# waltron.net
KiCad netlist of a schematic drawn in EAGLE
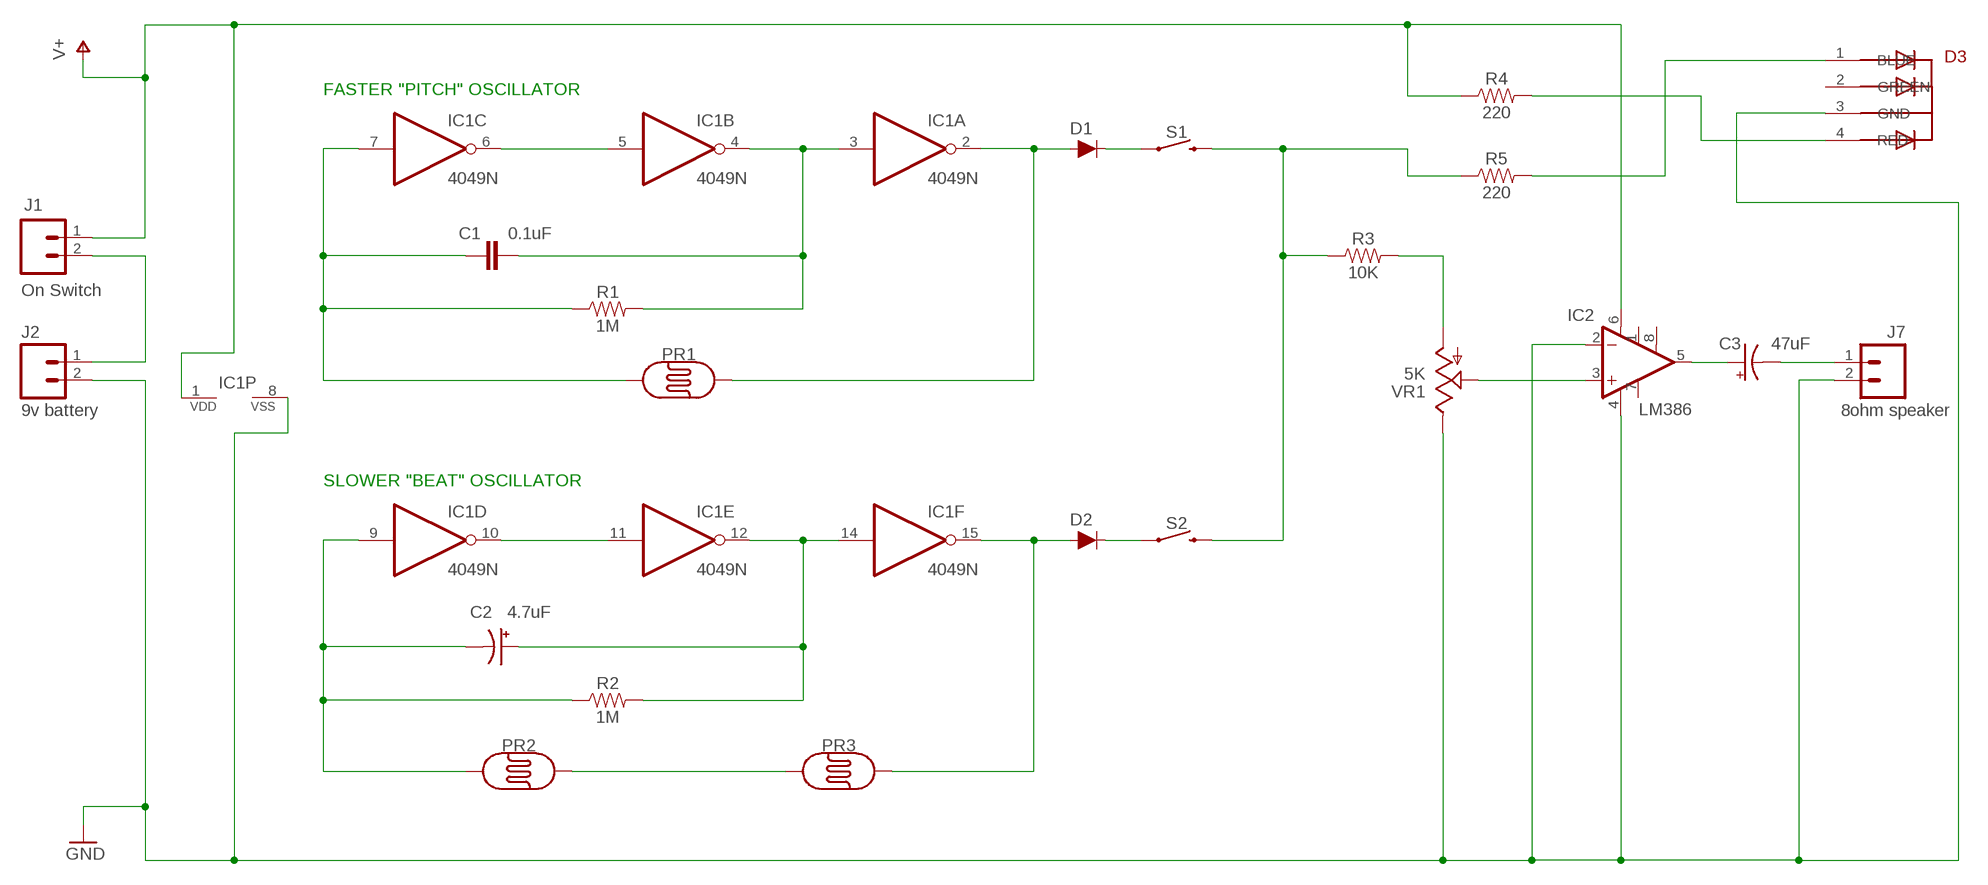
[diagram p0: schematic, sheet 1]

(export (version "E")
  (design (tool "Eeschema 10.0.6"))
  (components
    (comp (ref "C1")
      (value "0.1uF")
      (footprint "eagle-import:CAP-PTH-SMALL-KIT")
      (libsource (lib "eagle-import") (part "0.1UF-KIT-EZ-50V-20%"))
    )
    (comp (ref "C2")
      (value "4.7uF")
      (footprint "eagle-import:CPOL-RADIAL-2.5MM-5MM")
      (libsource (lib "eagle-import") (part "10UF-POLAR-RADIAL-2.5MM-25V-20%"))
    )
    (comp (ref "C3")
      (value "47uF")
      (footprint "eagle-import:CPOL-RADIAL-2.5MM-5MM")
      (libsource (lib "eagle-import") (part "10UF-POLAR-RADIAL-2.5MM-25V-20%"))
    )
    (comp (ref "D1")
      (value "DIODE-1N4148")
      (footprint "eagle-import:DIODE-1N4148")
      (libsource (lib "eagle-import") (part "DIODE-1N4148"))
    )
    (comp (ref "D2")
      (value "DIODE-1N4148")
      (footprint "eagle-import:DIODE-1N4148")
      (libsource (lib "eagle-import") (part "DIODE-1N4148"))
    )
    (comp (ref "D3")
      (value "5MMRGBLED")
      (footprint "eagle-import:LED5MMRGB")
      (libsource (lib "eagle-import") (part "5MMRGBLED"))
    )
    (comp (ref "IC1")
      (value "4049N")
      (footprint "eagle-import:DIL16")
      (libsource (lib "eagle-import") (part "4049N"))
    )
    (comp (ref "IC2")
      (value "LM386")
      (footprint "eagle-import:DIP08")
      (libsource (lib "eagle-import") (part "LM386"))
    )
    (comp (ref "J1")
      (value "On Switch")
      (footprint "eagle-import:1X02")
      (libsource (lib "eagle-import") (part "CONN_02"))
    )
    (comp (ref "J2")
      (value "9v battery")
      (footprint "eagle-import:1X02")
      (libsource (lib "eagle-import") (part "CONN_02"))
    )
    (comp (ref "J7")
      (value "8ohm speaker")
      (footprint "eagle-import:1X02")
      (libsource (lib "eagle-import") (part "CONN_02"))
    )
    (comp (ref "PR1")
      (value "PHOTOCELLPTH-KIT")
      (footprint "eagle-import:PHOTOCELL-KIT")
      (libsource (lib "eagle-import") (part "PHOTOCELLPTH-KIT"))
    )
    (comp (ref "PR2")
      (value "PHOTOCELLPTH-KIT")
      (footprint "eagle-import:PHOTOCELL-KIT")
      (libsource (lib "eagle-import") (part "PHOTOCELLPTH-KIT"))
    )
    (comp (ref "PR3")
      (value "PHOTOCELLPTH-KIT")
      (footprint "eagle-import:PHOTOCELL-KIT")
      (libsource (lib "eagle-import") (part "PHOTOCELLPTH-KIT"))
    )
    (comp (ref "R1")
      (value "1M")
      (footprint "eagle-import:AXIAL-0.3")
      (libsource (lib "eagle-import") (part "1KOHM-HORIZ-1/4W-1%"))
    )
    (comp (ref "R2")
      (value "1M")
      (footprint "eagle-import:AXIAL-0.3")
      (libsource (lib "eagle-import") (part "1KOHM-HORIZ-1/4W-1%"))
    )
    (comp (ref "R3")
      (value "10K")
      (footprint "eagle-import:AXIAL-0.3")
      (libsource (lib "eagle-import") (part "1KOHM-HORIZ-1/4W-1%"))
    )
    (comp (ref "R4")
      (value "220")
      (footprint "eagle-import:AXIAL-0.3")
      (libsource (lib "eagle-import") (part "1KOHM-HORIZ-1/4W-1%"))
    )
    (comp (ref "R5")
      (value "220")
      (footprint "eagle-import:AXIAL-0.3")
      (libsource (lib "eagle-import") (part "1KOHM-HORIZ-1/4W-1%"))
    )
    (comp (ref "S1")
      (value "MOMENTARY-SWITCH-SPST-PTH-6.0MM")
      (footprint "eagle-import:TACTILE_SWITCH_PTH_6.0MM")
      (libsource (lib "eagle-import") (part "MOMENTARY-SWITCH-SPST-PTH-6.0MM"))
    )
    (comp (ref "S2")
      (value "MOMENTARY-SWITCH-SPST-PTH-6.0MM")
      (footprint "eagle-import:TACTILE_SWITCH_PTH_6.0MM")
      (libsource (lib "eagle-import") (part "MOMENTARY-SWITCH-SPST-PTH-6.0MM"))
    )
    (comp (ref "VR1")
      (value "5K")
      (footprint "eagle-import:TRIM_POT")
      (libsource (lib "eagle-import") (part "POTTRIM"))
    )
  )
  (nets
    (net (code "1") (name "GND") (class "Default")
      (node (ref "D3") (pin "3") (pinfunction "GND_3") (pintype "bidirectional"))
      (node (ref "IC1") (pin "8") (pinfunction "VSS_8") (pintype "power_in"))
      (node (ref "IC2") (pin "2") (pinfunction "-IN_2") (pintype "input"))
      (node (ref "IC2") (pin "4") (pinfunction "V-_4") (pintype "power_in"))
      (node (ref "J2") (pin "2") (pinfunction "2_2") (pintype "passive"))
      (node (ref "J7") (pin "2") (pinfunction "2_2") (pintype "passive"))
      (node (ref "VR1") (pin "2") (pinfunction "E_2") (pintype "passive"))
    )
    (net (code "2") (name "Net-(C2-+)") (class "Default")
      (node (ref "C2") (pin "1") (pinfunction "+_1") (pintype "passive"))
      (node (ref "IC1") (pin "12") (pinfunction "O_12") (pintype "output"))
      (node (ref "IC1") (pin "14") (pinfunction "I_14") (pintype "input"))
      (node (ref "R2") (pin "P$2") (pinfunction "2_P$2") (pintype "passive"))
    )
    (net (code "3") (name "Net-(C2--)") (class "Default")
      (node (ref "C2") (pin "2") (pinfunction "-_2") (pintype "passive"))
      (node (ref "IC1") (pin "9") (pinfunction "I_9") (pintype "input"))
      (node (ref "PR2") (pin "1") (pinfunction "P$1_1") (pintype "bidirectional"))
      (node (ref "R2") (pin "P$1") (pinfunction "1_P$1") (pintype "passive"))
    )
    (net (code "4") (name "Net-(C3-+)") (class "Default")
      (node (ref "C3") (pin "1") (pinfunction "+_1") (pintype "passive"))
      (node (ref "IC2") (pin "5") (pinfunction "OUT_5") (pintype "output"))
    )
    (net (code "5") (name "Net-(C3--)") (class "Default")
      (node (ref "C3") (pin "2") (pinfunction "-_2") (pintype "passive"))
      (node (ref "J7") (pin "1") (pinfunction "1_1") (pintype "passive"))
    )
    (net (code "6") (name "Net-(D1-PadC)") (class "Default")
      (node (ref "D1") (pin "C") (pinfunction "C_C") (pintype "passive"))
      (node (ref "S1") (pin "1") (pinfunction "1_1") (pintype "passive"))
    )
    (net (code "7") (name "Net-(D2-PadC)") (class "Default")
      (node (ref "D2") (pin "C") (pinfunction "C_C") (pintype "passive"))
      (node (ref "S2") (pin "1") (pinfunction "1_1") (pintype "passive"))
    )
    (net (code "8") (name "Net-(D3-BLUE)") (class "Default")
      (node (ref "D3") (pin "1") (pinfunction "BLUE_1") (pintype "bidirectional"))
      (node (ref "R5") (pin "P$2") (pinfunction "2_P$2") (pintype "passive"))
    )
    (net (code "9") (name "Net-(D3-RED)") (class "Default")
      (node (ref "D3") (pin "4") (pinfunction "RED_4") (pintype "bidirectional"))
      (node (ref "R4") (pin "P$2") (pinfunction "2_P$2") (pintype "passive"))
    )
    (net (code "10") (name "Net-(IC1A-I)") (class "Default")
      (node (ref "C1") (pin "2") (pinfunction "2_2") (pintype "passive"))
      (node (ref "IC1") (pin "3") (pinfunction "I_3") (pintype "input"))
      (node (ref "IC1") (pin "4") (pinfunction "O_4") (pintype "output"))
      (node (ref "R1") (pin "P$2") (pinfunction "2_P$2") (pintype "passive"))
    )
    (net (code "11") (name "Net-(IC1A-O)") (class "Default")
      (node (ref "D1") (pin "A") (pinfunction "A_A") (pintype "passive"))
      (node (ref "IC1") (pin "2") (pinfunction "O_2") (pintype "output"))
      (node (ref "PR1") (pin "2") (pinfunction "P$2_2") (pintype "bidirectional"))
    )
    (net (code "12") (name "Net-(IC1B-I)") (class "Default")
      (node (ref "IC1") (pin "5") (pinfunction "I_5") (pintype "input"))
      (node (ref "IC1") (pin "6") (pinfunction "O_6") (pintype "output"))
    )
    (net (code "13") (name "Net-(IC1C-I)") (class "Default")
      (node (ref "C1") (pin "1") (pinfunction "1_1") (pintype "passive"))
      (node (ref "IC1") (pin "7") (pinfunction "I_7") (pintype "input"))
      (node (ref "PR1") (pin "1") (pinfunction "P$1_1") (pintype "bidirectional"))
      (node (ref "R1") (pin "P$1") (pinfunction "1_P$1") (pintype "passive"))
    )
    (net (code "14") (name "Net-(IC1D-O)") (class "Default")
      (node (ref "IC1") (pin "10") (pinfunction "O_10") (pintype "output"))
      (node (ref "IC1") (pin "11") (pinfunction "I_11") (pintype "input"))
    )
    (net (code "15") (name "Net-(IC1F-O)") (class "Default")
      (node (ref "D2") (pin "A") (pinfunction "A_A") (pintype "passive"))
      (node (ref "IC1") (pin "15") (pinfunction "O_15") (pintype "output"))
      (node (ref "PR3") (pin "2") (pinfunction "P$2_2") (pintype "bidirectional"))
    )
    (net (code "16") (name "Net-(IC2-+IN)") (class "Default")
      (node (ref "IC2") (pin "3") (pinfunction "+IN_3") (pintype "input"))
      (node (ref "VR1") (pin "1") (pinfunction "S_1") (pintype "passive"))
    )
    (net (code "17") (name "Net-(J1-Pad2)") (class "Default")
      (node (ref "J1") (pin "2") (pinfunction "2_2") (pintype "passive"))
      (node (ref "J2") (pin "1") (pinfunction "1_1") (pintype "passive"))
    )
    (net (code "18") (name "Net-(PR2-P$2)") (class "Default")
      (node (ref "PR2") (pin "2") (pinfunction "P$2_2") (pintype "bidirectional"))
      (node (ref "PR3") (pin "1") (pinfunction "P$1_1") (pintype "bidirectional"))
    )
    (net (code "19") (name "Net-(R3-1)") (class "Default")
      (node (ref "R3") (pin "P$1") (pinfunction "1_P$1") (pintype "passive"))
      (node (ref "R5") (pin "P$1") (pinfunction "1_P$1") (pintype "passive"))
      (node (ref "S1") (pin "3") (pinfunction "2_3") (pintype "passive"))
      (node (ref "S2") (pin "3") (pinfunction "2_3") (pintype "passive"))
    )
    (net (code "20") (name "Net-(R3-2)") (class "Default")
      (node (ref "R3") (pin "P$2") (pinfunction "2_P$2") (pintype "passive"))
      (node (ref "VR1") (pin "3") (pinfunction "A_3") (pintype "passive"))
    )
    (net (code "21") (name "V+") (class "Default")
      (node (ref "IC1") (pin "1") (pinfunction "VDD_1") (pintype "power_in"))
      (node (ref "IC2") (pin "6") (pinfunction "V+_6") (pintype "power_in"))
      (node (ref "J1") (pin "1") (pinfunction "1_1") (pintype "passive"))
      (node (ref "R4") (pin "P$1") (pinfunction "1_P$1") (pintype "passive"))
    )
    (net (code "22") (name "unconnected-(D3-GREEN-Pad2)") (class "Default")
      (node (ref "D3") (pin "2") (pinfunction "GREEN_2") (pintype "bidirectional"))
    )
    (net (code "23") (name "unconnected-(IC2-BP-Pad7)") (class "Default")
      (node (ref "IC2") (pin "7") (pinfunction "BP_7") (pintype "bidirectional"))
    )
    (net (code "24") (name "unconnected-(IC2-GAIN-Pad1)") (class "Default")
      (node (ref "IC2") (pin "1") (pinfunction "GAIN_1") (pintype "bidirectional"))
    )
    (net (code "25") (name "unconnected-(IC2-GAIN-Pad8)") (class "Default")
      (node (ref "IC2") (pin "8") (pinfunction "GAIN_8") (pintype "bidirectional"))
    )
  )
)
